# femtoUSB_r1_0_0_TQFP.net
KiCad netlist of a schematic drawn in EAGLE
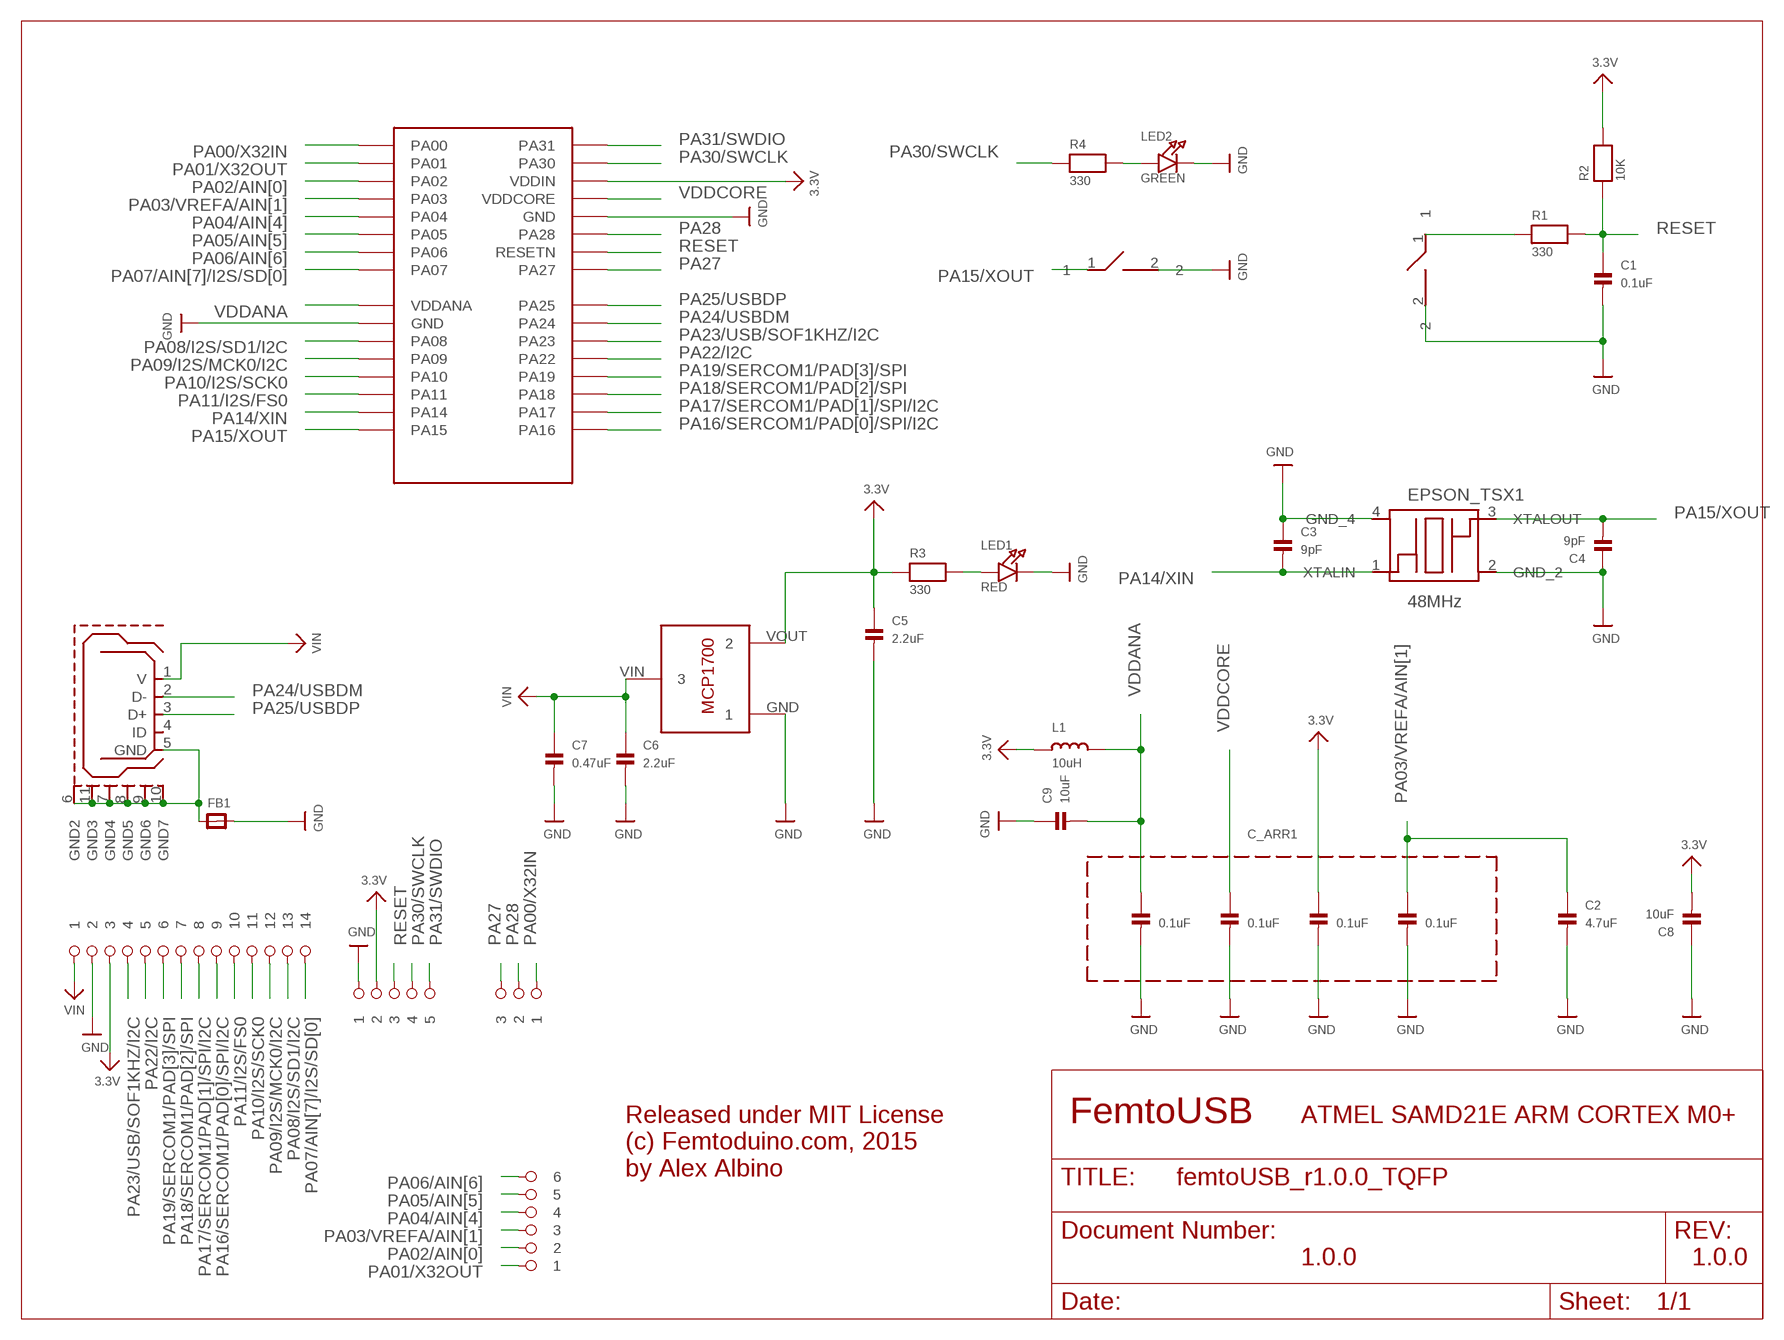
[diagram p0: schematic, sheet 1]

(export (version "E")
  (design (tool "Eeschema 10.0.6"))
  (components
    (comp (ref "BTN")
      (value "OMRON B3U-300P(M)")
      (footprint "eagle-import:SPST_SMD")
      (libsource (lib "eagle-import") (part "SPST_SMD"))
    )
    (comp (ref "C1")
      (value "0.1uF")
      (footprint "eagle-import:_0402MP")
      (fields (field (name "DIGIKEY_PART") "445-4958-1-ND"))
      (libsource (lib "eagle-import") (part "CAP_CERAMIC_0402MP"))
    )
    (comp (ref "C2")
      (value "4.7uF")
      (footprint "eagle-import:_0402MP")
      (libsource (lib "eagle-import") (part "CAP_CERAMIC_0402MP"))
    )
    (comp (ref "C3")
      (value "9pF")
      (footprint "eagle-import:_0402MP")
      (libsource (lib "eagle-import") (part "CAP_CERAMIC_0402MP"))
    )
    (comp (ref "C4")
      (value "9pF")
      (footprint "eagle-import:_0402MP")
      (libsource (lib "eagle-import") (part "CAP_CERAMIC_0402MP"))
    )
    (comp (ref "C5")
      (value "2.2uF")
      (footprint "eagle-import:_0402MP")
      (libsource (lib "eagle-import") (part "CAP_CERAMIC_0402MP"))
    )
    (comp (ref "C6")
      (value "2.2uF")
      (footprint "eagle-import:_0402MP")
      (libsource (lib "eagle-import") (part "CAP_CERAMIC_0402MP"))
    )
    (comp (ref "C7")
      (value "0.47uF")
      (footprint "eagle-import:_0402MP")
      (libsource (lib "eagle-import") (part "CAP_CERAMIC_0402MP"))
    )
    (comp (ref "C8")
      (value "10uF")
      (footprint "eagle-import:_0402MP")
      (libsource (lib "eagle-import") (part "CAP_CERAMIC_0402MP"))
    )
    (comp (ref "C9")
      (value "10uF")
      (footprint "eagle-import:_0402MP")
      (libsource (lib "eagle-import") (part "CAP_CERAMIC_0402MP"))
    )
    (comp (ref "C_ARR1")
      (value "0.1uF")
      (footprint "eagle-import:CAPACITOR_ARRAY_1206_MONO_1X4")
      (libsource (lib "eagle-import") (part "KEMET_CERAMIC_CAPACITOR_ARRAY_1X4"))
    )
    (comp (ref "EPSON_TSX1")
      (value "48MHz")
      (footprint "eagle-import:TSX-3225")
      (fields (field (name "DIGIKEY_PART") "TSX-3225 32.0000MF15X-B-ND"))
      (libsource (lib "eagle-import") (part "TSX-3225"))
    )
    (comp (ref "FB1")
      (value "FERRITE_0603MP")
      (footprint "eagle-import:_0603MP")
      (libsource (lib "eagle-import") (part "FERRITE_0603MP"))
    )
    (comp (ref "IC1")
      (value "ATSAMD21E18A-AU")
      (footprint "eagle-import:32-TQFP")
      (fields (field (name "DIGIKEY_PART") "ATSAMD21E18A-AU-ND"))
      (libsource (lib "eagle-import") (part "ATSAMD21E18A-AU"))
    )
    (comp (ref "L1")
      (value "10uH")
      (footprint "eagle-import:_0603MP")
      (libsource (lib "eagle-import") (part "INDUCTOR_0603MP"))
    )
    (comp (ref "LDO_VREG")
      (value "MCP1700T-3302E/TT")
      (footprint "eagle-import:MCP1700T-3302E_TT")
      (libsource (lib "eagle-import") (part "MCP1700T-3302E/TT"))
    )
    (comp (ref "LED1")
      (value "RED")
      (footprint "eagle-import:CHIPLED_0603_NOOUTLINE")
      (libsource (lib "eagle-import") (part "LED0603_NOOUTLINE"))
    )
    (comp (ref "LED2")
      (value "GREEN")
      (footprint "eagle-import:CHIPLED_0603_NOOUTLINE")
      (libsource (lib "eagle-import") (part "LED0603_NOOUTLINE"))
    )
    (comp (ref "MICRO_B_USB")
      (value "USB_MICROB")
      (footprint "eagle-import:USB_MICROB_PACKAGE")
      (libsource (lib "eagle-import") (part "USB_MICROB"))
    )
    (comp (ref "R1")
      (value "330")
      (footprint "eagle-import:_0402MP")
      (fields (field (name "DIGIKEY_PART") "541-330JCT-ND"))
      (libsource (lib "eagle-import") (part "RESISTOR_0402MP"))
    )
    (comp (ref "R2")
      (value "10K")
      (footprint "eagle-import:_0402MP")
      (libsource (lib "eagle-import") (part "RESISTOR_0402MP"))
    )
    (comp (ref "R3")
      (value "330")
      (footprint "eagle-import:_0402MP")
      (libsource (lib "eagle-import") (part "RESISTOR_0402MP"))
    )
    (comp (ref "R4")
      (value "330")
      (footprint "eagle-import:_0402MP")
      (libsource (lib "eagle-import") (part "RESISTOR_0402MP"))
    )
    (comp (ref "U$6")
      (value "1X14_ROUND")
      (footprint "eagle-import:1X14_ROUND")
      (libsource (lib "eagle-import") (part "1X14_ROUND"))
    )
    (comp (ref "U$7")
      (value "1X3_ROUND")
      (footprint "eagle-import:1X3_ROUND")
      (libsource (lib "eagle-import") (part "1X3_ROUND"))
    )
    (comp (ref "U$9")
      (value "1X5_ROUND")
      (footprint "eagle-import:1X5_ROUND")
      (libsource (lib "eagle-import") (part "1X5_ROUND"))
    )
    (comp (ref "U$12")
      (value "1X6_ROUND")
      (footprint "eagle-import:1X6_ROUND")
      (libsource (lib "eagle-import") (part "1X6_ROUND"))
    )
    (comp (ref "U$38")
      (value "SPST_SMD")
      (footprint "eagle-import:SPST_SMD")
      (libsource (lib "eagle-import") (part "SPST_SMD"))
    )
  )
  (nets
    (net (code "1") (name "/PA00{slash}X32IN") (class "Default")
      (node (ref "IC1") (pin "1") (pinfunction "PA00_1") (pintype "bidirectional"))
      (node (ref "U$7") (pin "P$1") (pinfunction "1_P$1") (pintype "bidirectional"))
    )
    (net (code "2") (name "/PA01{slash}X32OUT") (class "Default")
      (node (ref "IC1") (pin "2") (pinfunction "PA01_2") (pintype "bidirectional"))
      (node (ref "U$12") (pin "P$1") (pinfunction "1_P$1") (pintype "bidirectional"))
    )
    (net (code "3") (name "/PA02{slash}AIN[0]") (class "Default")
      (node (ref "IC1") (pin "3") (pinfunction "PA02_3") (pintype "bidirectional"))
      (node (ref "U$12") (pin "P$2") (pinfunction "2_P$2") (pintype "bidirectional"))
    )
    (net (code "4") (name "/PA03{slash}VREFA{slash}AIN[1]") (class "Default")
      (node (ref "C2") (pin "1") (pinfunction "P$1_1") (pintype "passive"))
      (node (ref "C_ARR1") (pin "7") (pinfunction "P$7_7") (pintype "passive"))
      (node (ref "IC1") (pin "4") (pinfunction "PA03_4") (pintype "bidirectional"))
      (node (ref "U$12") (pin "P$3") (pinfunction "3_P$3") (pintype "bidirectional"))
    )
    (net (code "5") (name "/PA04{slash}AIN[4]") (class "Default")
      (node (ref "IC1") (pin "5") (pinfunction "PA04_5") (pintype "bidirectional"))
      (node (ref "U$12") (pin "P$4") (pinfunction "4_P$4") (pintype "bidirectional"))
    )
    (net (code "6") (name "/PA05{slash}AIN[5]") (class "Default")
      (node (ref "IC1") (pin "6") (pinfunction "PA05_6") (pintype "bidirectional"))
      (node (ref "U$12") (pin "P$5") (pinfunction "5_P$5") (pintype "bidirectional"))
    )
    (net (code "7") (name "/PA06{slash}AIN[6]") (class "Default")
      (node (ref "IC1") (pin "7") (pinfunction "PA06_7") (pintype "bidirectional"))
      (node (ref "U$12") (pin "P$6") (pinfunction "6_P$6") (pintype "bidirectional"))
    )
    (net (code "8") (name "/PA07{slash}AIN[7]{slash}I2S{slash}SD[0]") (class "Default")
      (node (ref "IC1") (pin "8") (pinfunction "PA07_8") (pintype "bidirectional"))
      (node (ref "U$6") (pin "P$14") (pinfunction "14_P$14") (pintype "bidirectional"))
    )
    (net (code "9") (name "/PA08{slash}I2S{slash}SD1{slash}I2C") (class "Default")
      (node (ref "IC1") (pin "11") (pinfunction "PA08_11") (pintype "bidirectional"))
      (node (ref "U$6") (pin "P$13") (pinfunction "13_P$13") (pintype "bidirectional"))
    )
    (net (code "10") (name "/PA09{slash}I2S{slash}MCK0{slash}I2C") (class "Default")
      (node (ref "IC1") (pin "12") (pinfunction "PA09_12") (pintype "bidirectional"))
      (node (ref "U$6") (pin "P$12") (pinfunction "12_P$12") (pintype "bidirectional"))
    )
    (net (code "11") (name "/PA10{slash}I2S{slash}SCK0") (class "Default")
      (node (ref "IC1") (pin "13") (pinfunction "PA10_13") (pintype "bidirectional"))
      (node (ref "U$6") (pin "P$11") (pinfunction "11_P$11") (pintype "bidirectional"))
    )
    (net (code "12") (name "/PA11{slash}I2S{slash}FS0") (class "Default")
      (node (ref "IC1") (pin "14") (pinfunction "PA11_14") (pintype "bidirectional"))
      (node (ref "U$6") (pin "P$10") (pinfunction "10_P$10") (pintype "bidirectional"))
    )
    (net (code "13") (name "/PA14{slash}XIN") (class "Default")
      (node (ref "C3") (pin "2") (pinfunction "P$2_2") (pintype "passive"))
      (node (ref "EPSON_TSX1") (pin "1") (pinfunction "XTALIN_1") (pintype "bidirectional"))
      (node (ref "IC1") (pin "15") (pinfunction "PA14_15") (pintype "bidirectional"))
    )
    (net (code "14") (name "/PA15{slash}XOUT") (class "Default")
      (node (ref "C4") (pin "2") (pinfunction "P$2_2") (pintype "passive"))
      (node (ref "EPSON_TSX1") (pin "3") (pinfunction "XTALOUT_3") (pintype "bidirectional"))
      (node (ref "IC1") (pin "16") (pinfunction "PA15_16") (pintype "bidirectional"))
      (node (ref "U$38") (pin "1") (pinfunction "1_1") (pintype "bidirectional"))
    )
    (net (code "15") (name "/PA16{slash}SERCOM1{slash}PAD[0]{slash}SPI{slash}I2C") (class "Default")
      (node (ref "IC1") (pin "17") (pinfunction "PA16_17") (pintype "bidirectional"))
      (node (ref "U$6") (pin "P$9") (pinfunction "9_P$9") (pintype "bidirectional"))
    )
    (net (code "16") (name "/PA17{slash}SERCOM1{slash}PAD[1]{slash}SPI{slash}I2C") (class "Default")
      (node (ref "IC1") (pin "18") (pinfunction "PA17_18") (pintype "bidirectional"))
      (node (ref "U$6") (pin "P$8") (pinfunction "8_P$8") (pintype "bidirectional"))
    )
    (net (code "17") (name "/PA18{slash}SERCOM1{slash}PAD[2]{slash}SPI") (class "Default")
      (node (ref "IC1") (pin "19") (pinfunction "PA18_19") (pintype "bidirectional"))
      (node (ref "U$6") (pin "P$7") (pinfunction "7_P$7") (pintype "bidirectional"))
    )
    (net (code "18") (name "/PA19{slash}SERCOM1{slash}PAD[3]{slash}SPI") (class "Default")
      (node (ref "IC1") (pin "20") (pinfunction "PA19_20") (pintype "bidirectional"))
      (node (ref "U$6") (pin "P$6") (pinfunction "6_P$6") (pintype "bidirectional"))
    )
    (net (code "19") (name "/PA22{slash}I2C") (class "Default")
      (node (ref "IC1") (pin "21") (pinfunction "PA22_21") (pintype "bidirectional"))
      (node (ref "U$6") (pin "P$5") (pinfunction "5_P$5") (pintype "bidirectional"))
    )
    (net (code "20") (name "/PA23{slash}USB{slash}SOF1KHZ{slash}I2C") (class "Default")
      (node (ref "IC1") (pin "22") (pinfunction "PA23_22") (pintype "bidirectional"))
      (node (ref "U$6") (pin "P$4") (pinfunction "4_P$4") (pintype "bidirectional"))
    )
    (net (code "21") (name "/PA24{slash}USBDM") (class "Default")
      (node (ref "IC1") (pin "23") (pinfunction "PA24_23") (pintype "bidirectional"))
      (node (ref "MICRO_B_USB") (pin "2") (pinfunction "D-_2") (pintype "bidirectional"))
    )
    (net (code "22") (name "/PA25{slash}USBDP") (class "Default")
      (node (ref "IC1") (pin "24") (pinfunction "PA25_24") (pintype "bidirectional"))
      (node (ref "MICRO_B_USB") (pin "3") (pinfunction "D+_3") (pintype "bidirectional"))
    )
    (net (code "23") (name "/PA27") (class "Default")
      (node (ref "IC1") (pin "25") (pinfunction "PA27_25") (pintype "bidirectional"))
      (node (ref "U$7") (pin "P$3") (pinfunction "3_P$3") (pintype "bidirectional"))
    )
    (net (code "24") (name "/PA28") (class "Default")
      (node (ref "IC1") (pin "27") (pinfunction "PA28_27") (pintype "bidirectional"))
      (node (ref "U$7") (pin "P$2") (pinfunction "2_P$2") (pintype "bidirectional"))
    )
    (net (code "25") (name "/PA30{slash}SWCLK") (class "Default")
      (node (ref "IC1") (pin "31") (pinfunction "PA30_31") (pintype "bidirectional"))
      (node (ref "R4") (pin "1") (pinfunction "1_1") (pintype "passive"))
      (node (ref "U$9") (pin "P$4") (pinfunction "4_P$4") (pintype "bidirectional"))
    )
    (net (code "26") (name "/PA31{slash}SWDIO") (class "Default")
      (node (ref "IC1") (pin "32") (pinfunction "PA31_32") (pintype "bidirectional"))
      (node (ref "U$9") (pin "P$5") (pinfunction "5_P$5") (pintype "bidirectional"))
    )
    (net (code "27") (name "/RESET") (class "Default")
      (node (ref "C1") (pin "1") (pinfunction "P$1_1") (pintype "passive"))
      (node (ref "IC1") (pin "26") (pinfunction "RESETN_26") (pintype "bidirectional"))
      (node (ref "R1") (pin "2") (pinfunction "2_2") (pintype "passive"))
      (node (ref "R2") (pin "1") (pinfunction "1_1") (pintype "passive"))
      (node (ref "U$9") (pin "P$3") (pinfunction "3_P$3") (pintype "bidirectional"))
    )
    (net (code "28") (name "/VDDANA") (class "Default")
      (node (ref "C9") (pin "2") (pinfunction "P$2_2") (pintype "passive"))
      (node (ref "C_ARR1") (pin "1") (pinfunction "P$1_1") (pintype "passive"))
      (node (ref "IC1") (pin "9") (pinfunction "VDDANA_9") (pintype "bidirectional"))
      (node (ref "L1") (pin "2") (pinfunction "2_2") (pintype "passive"))
    )
    (net (code "29") (name "/VDDCORE") (class "Default")
      (node (ref "C_ARR1") (pin "3") (pinfunction "P$3_3") (pintype "passive"))
      (node (ref "IC1") (pin "29") (pinfunction "VDDCORE_29") (pintype "bidirectional"))
    )
    (net (code "30") (name "3.3V") (class "Default")
      (node (ref "C5") (pin "1") (pinfunction "P$1_1") (pintype "passive"))
      (node (ref "C8") (pin "2") (pinfunction "P$2_2") (pintype "passive"))
      (node (ref "C_ARR1") (pin "5") (pinfunction "P$5_5") (pintype "passive"))
      (node (ref "IC1") (pin "30") (pinfunction "VDDIN_30") (pintype "bidirectional"))
      (node (ref "L1") (pin "1") (pinfunction "1_1") (pintype "passive"))
      (node (ref "LDO_VREG") (pin "VOUT") (pinfunction "2_VOUT") (pintype "bidirectional"))
      (node (ref "R2") (pin "2") (pinfunction "2_2") (pintype "passive"))
      (node (ref "R3") (pin "1") (pinfunction "1_1") (pintype "passive"))
      (node (ref "U$6") (pin "P$3") (pinfunction "3_P$3") (pintype "bidirectional"))
      (node (ref "U$9") (pin "P$2") (pinfunction "2_P$2") (pintype "bidirectional"))
    )
    (net (code "31") (name "GND") (class "Default")
      (node (ref "BTN") (pin "2") (pinfunction "2_2") (pintype "bidirectional"))
      (node (ref "C1") (pin "2") (pinfunction "P$2_2") (pintype "passive"))
      (node (ref "C2") (pin "2") (pinfunction "P$2_2") (pintype "passive"))
      (node (ref "C3") (pin "1") (pinfunction "P$1_1") (pintype "passive"))
      (node (ref "C4") (pin "1") (pinfunction "P$1_1") (pintype "passive"))
      (node (ref "C5") (pin "2") (pinfunction "P$2_2") (pintype "passive"))
      (node (ref "C6") (pin "2") (pinfunction "P$2_2") (pintype "passive"))
      (node (ref "C7") (pin "2") (pinfunction "P$2_2") (pintype "passive"))
      (node (ref "C8") (pin "1") (pinfunction "P$1_1") (pintype "passive"))
      (node (ref "C9") (pin "1") (pinfunction "P$1_1") (pintype "passive"))
      (node (ref "C_ARR1") (pin "2") (pinfunction "P$2_2") (pintype "passive"))
      (node (ref "C_ARR1") (pin "4") (pinfunction "P$4_4") (pintype "passive"))
      (node (ref "C_ARR1") (pin "6") (pinfunction "P$6_6") (pintype "passive"))
      (node (ref "C_ARR1") (pin "8") (pinfunction "P$8_8") (pintype "passive"))
      (node (ref "EPSON_TSX1") (pin "2") (pinfunction "GND_2_2") (pintype "bidirectional"))
      (node (ref "EPSON_TSX1") (pin "4") (pinfunction "GND_4_4") (pintype "bidirectional"))
      (node (ref "FB1") (pin "2") (pinfunction "P$2_2") (pintype "passive"))
      (node (ref "IC1") (pin "10") (pinfunction "GND_10") (pintype "bidirectional"))
      (node (ref "IC1") (pin "28") (pinfunction "GND_28") (pintype "bidirectional"))
      (node (ref "LDO_VREG") (pin "GND") (pinfunction "1_GND") (pintype "bidirectional"))
      (node (ref "LED1") (pin "C") (pinfunction "C_C") (pintype "passive"))
      (node (ref "LED2") (pin "C") (pinfunction "C_C") (pintype "passive"))
      (node (ref "U$38") (pin "2") (pinfunction "2_2") (pintype "bidirectional"))
      (node (ref "U$6") (pin "P$2") (pinfunction "2_P$2") (pintype "bidirectional"))
      (node (ref "U$9") (pin "P$1") (pinfunction "1_P$1") (pintype "bidirectional"))
    )
    (net (code "32") (name "Net-(BTN-Pad1)") (class "Default")
      (node (ref "BTN") (pin "1") (pinfunction "1_1") (pintype "bidirectional"))
      (node (ref "R1") (pin "1") (pinfunction "1_1") (pintype "passive"))
    )
    (net (code "33") (name "Net-(FB1-P$1)") (class "Default")
      (node (ref "FB1") (pin "1") (pinfunction "P$1_1") (pintype "passive"))
      (node (ref "MICRO_B_USB") (pin "10") (pinfunction "GND7_10") (pintype "bidirectional"))
      (node (ref "MICRO_B_USB") (pin "11") (pinfunction "GND3_11") (pintype "bidirectional"))
      (node (ref "MICRO_B_USB") (pin "5") (pinfunction "GND_5") (pintype "bidirectional"))
      (node (ref "MICRO_B_USB") (pin "6") (pinfunction "GND2_6") (pintype "bidirectional"))
      (node (ref "MICRO_B_USB") (pin "7") (pinfunction "GND4_7") (pintype "bidirectional"))
      (node (ref "MICRO_B_USB") (pin "8") (pinfunction "GND5_8") (pintype "bidirectional"))
      (node (ref "MICRO_B_USB") (pin "9") (pinfunction "GND6_9") (pintype "bidirectional"))
    )
    (net (code "34") (name "Net-(LED1-PadA)") (class "Default")
      (node (ref "LED1") (pin "A") (pinfunction "A_A") (pintype "passive"))
      (node (ref "R3") (pin "2") (pinfunction "2_2") (pintype "passive"))
    )
    (net (code "35") (name "Net-(LED2-PadA)") (class "Default")
      (node (ref "LED2") (pin "A") (pinfunction "A_A") (pintype "passive"))
      (node (ref "R4") (pin "2") (pinfunction "2_2") (pintype "passive"))
    )
    (net (code "36") (name "VIN") (class "Default")
      (node (ref "C6") (pin "1") (pinfunction "P$1_1") (pintype "passive"))
      (node (ref "C7") (pin "1") (pinfunction "P$1_1") (pintype "passive"))
      (node (ref "LDO_VREG") (pin "VIN") (pinfunction "3_VIN") (pintype "bidirectional"))
      (node (ref "MICRO_B_USB") (pin "1") (pinfunction "V_1") (pintype "bidirectional"))
      (node (ref "U$6") (pin "P$1") (pinfunction "1_P$1") (pintype "bidirectional"))
    )
    (net (code "37") (name "unconnected-(MICRO_B_USB-ID-Pad4)") (class "Default")
      (node (ref "MICRO_B_USB") (pin "4") (pinfunction "ID_4") (pintype "bidirectional"))
    )
  )
)
